# ct_psu.net
KiCad netlist of a schematic drawn in Altium Designer
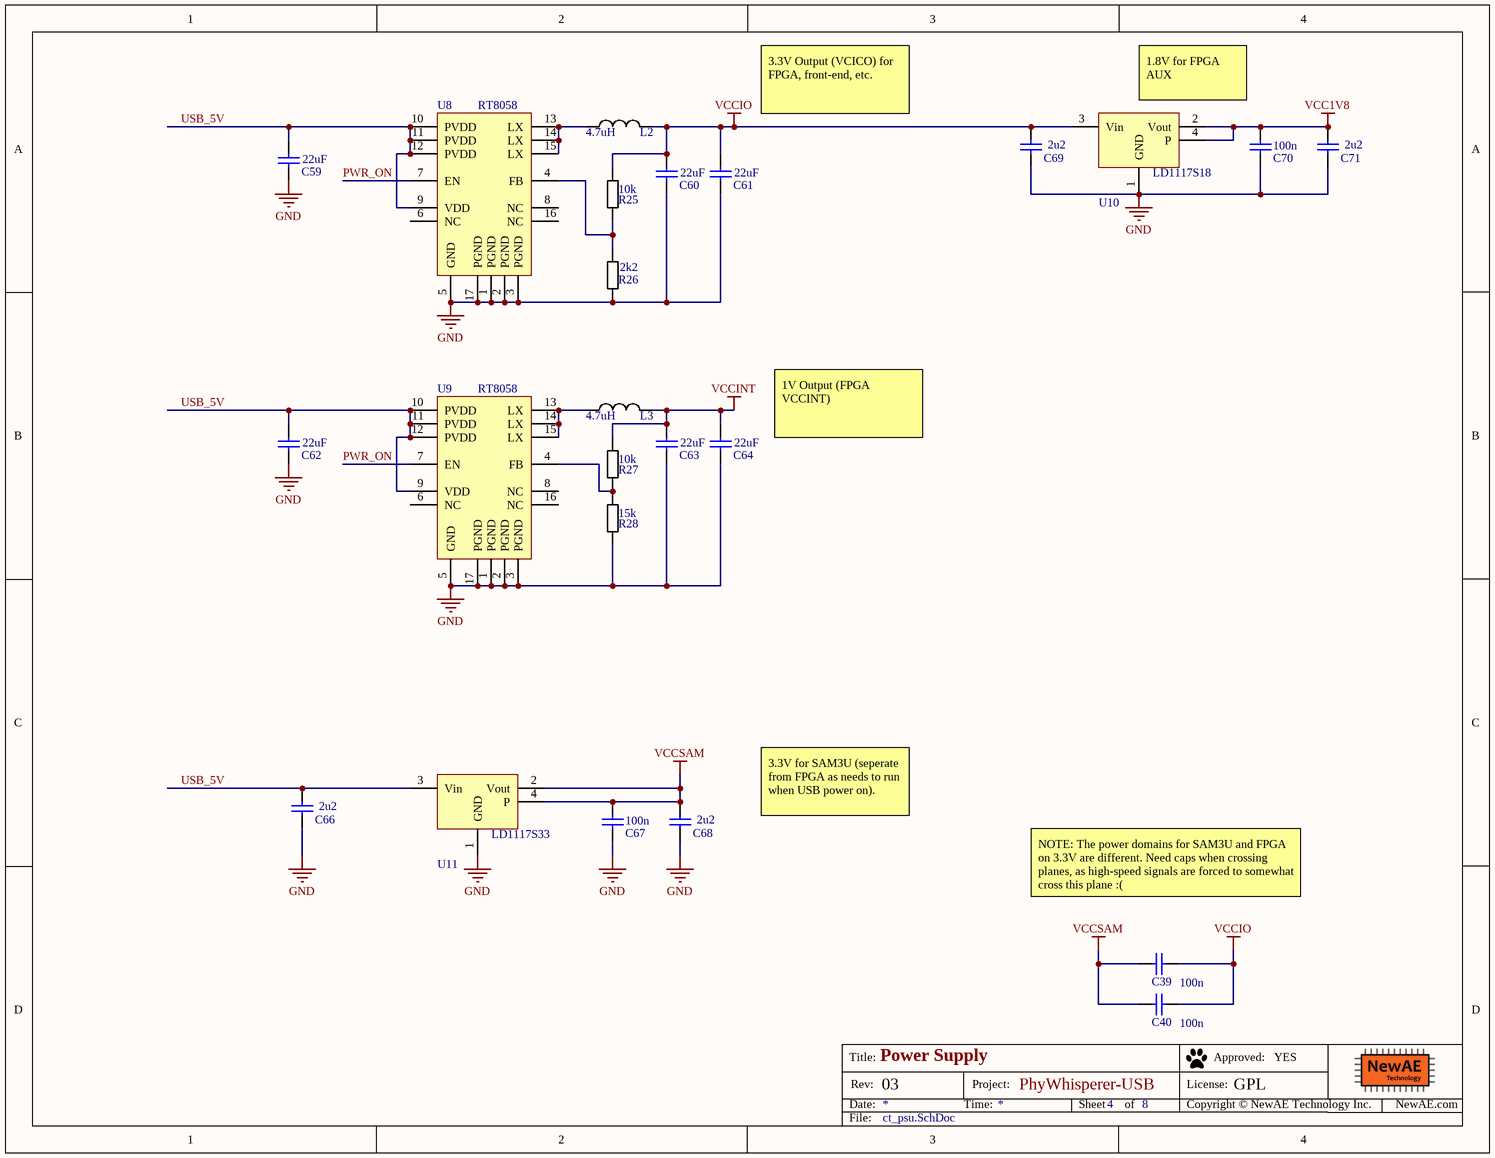
[diagram p0: ct_psu.SchDoc]

(export (version "E")
  (design (tool "Eeschema 10.0.6"))
  (components
    (comp (ref "C39")
      (value "100n")
      (footprint "CAPC0603_M")
      (description "100n, 0603")
      (fields (field (name "PART NUMBER") "CCHIP-100n-0603"))
      (libsource (lib "NewAE_AltiumLib") (part "CAP"))
    )
    (comp (ref "C40")
      (value "100n")
      (footprint "CAPC0603_M")
      (description "100n, 0603")
      (fields (field (name "PART NUMBER") "CCHIP-100n-0603"))
      (libsource (lib "NewAE_AltiumLib") (part "CAP"))
    )
    (comp (ref "C59")
      (value "22uF")
      (footprint "CAPC0805_M")
      (description "22u, 16V, 0805, Ceramic")
      (fields (field (name "PART NUMBER") "CCHIP-22u-0805-16V") (field (name "TOLERANCE") "20%"))
      (libsource (lib "NewAE_AltiumLib") (part "CAP"))
    )
    (comp (ref "C60")
      (value "22uF")
      (footprint "CAPC0805_M")
      (description "22u, 16V, 0805, Ceramic")
      (fields (field (name "PART NUMBER") "CCHIP-22u-0805-16V") (field (name "TOLERANCE") "20%"))
      (libsource (lib "NewAE_AltiumLib") (part "CAP"))
    )
    (comp (ref "C61")
      (value "22uF")
      (footprint "CAPC0805_M")
      (description "22u, 16V, 0805, Ceramic")
      (fields (field (name "PART NUMBER") "CCHIP-22u-0805-16V") (field (name "TOLERANCE") "20%"))
      (libsource (lib "NewAE_AltiumLib") (part "CAP"))
    )
    (comp (ref "C62")
      (value "22uF")
      (footprint "CAPC0805_M")
      (description "22u, 16V, 0805, Ceramic")
      (fields (field (name "PART NUMBER") "CCHIP-22u-0805-16V") (field (name "TOLERANCE") "20%"))
      (libsource (lib "NewAE_AltiumLib") (part "CAP"))
    )
    (comp (ref "C63")
      (value "22uF")
      (footprint "CAPC0805_M")
      (description "22u, 16V, 0805, Ceramic")
      (fields (field (name "PART NUMBER") "CCHIP-22u-0805-16V") (field (name "TOLERANCE") "20%"))
      (libsource (lib "NewAE_AltiumLib") (part "CAP"))
    )
    (comp (ref "C64")
      (value "22uF")
      (footprint "CAPC0805_M")
      (description "22u, 16V, 0805, Ceramic")
      (fields (field (name "PART NUMBER") "CCHIP-22u-0805-16V") (field (name "TOLERANCE") "20%"))
      (libsource (lib "NewAE_AltiumLib") (part "CAP"))
    )
    (comp (ref "C66")
      (value "2u2")
      (footprint "CAPC0603_M")
      (description "2u2, 0603")
      (fields (field (name "PART NUMBER") "CCHIP-2u2-0603"))
      (libsource (lib "NewAE_AltiumLib") (part "CAP"))
    )
    (comp (ref "C67")
      (value "100n")
      (footprint "CAPC0402_M")
      (description "100n, 0402")
      (fields (field (name "PART NUMBER") "CCHIP-100n-0402"))
      (libsource (lib "NewAE_AltiumLib") (part "CAP"))
    )
    (comp (ref "C68")
      (value "2u2")
      (footprint "CAPC0603_M")
      (description "2u2, 0603")
      (fields (field (name "PART NUMBER") "CCHIP-2u2-0603"))
      (libsource (lib "NewAE_AltiumLib") (part "CAP"))
    )
    (comp (ref "C69")
      (value "2u2")
      (footprint "CAPC0603_M")
      (description "2u2, 0603")
      (fields (field (name "PART NUMBER") "CCHIP-2u2-0603"))
      (libsource (lib "NewAE_AltiumLib") (part "CAP"))
    )
    (comp (ref "C70")
      (value "100n")
      (footprint "CAPC0402_M")
      (description "100n, 0402")
      (fields (field (name "PART NUMBER") "CCHIP-100n-0402"))
      (libsource (lib "NewAE_AltiumLib") (part "CAP"))
    )
    (comp (ref "C71")
      (value "2u2")
      (footprint "CAPC0603_M")
      (description "2u2, 0603")
      (fields (field (name "PART NUMBER") "CCHIP-2u2-0603"))
      (libsource (lib "NewAE_AltiumLib") (part "CAP"))
    )
    (comp (ref "L2")
      (value "4.7uH")
      (footprint "NR6028")
      (description "fixed ind, ferrite, shielded")
      (fields (field (name "PART NUMBER") "NR6028T4R7M"))
      (libsource (lib "NewAE_AltiumLib") (part "IND"))
    )
    (comp (ref "L3")
      (value "4.7uH")
      (footprint "NR6028")
      (description "fixed ind, ferrite, shielded")
      (fields (field (name "PART NUMBER") "NR6028T4R7M"))
      (libsource (lib "NewAE_AltiumLib") (part "IND"))
    )
    (comp (ref "R25")
      (value "10k")
      (footprint "RESC1608X55N")
      (description "10k res, 0603, 1%, 1/10W")
      (fields (field (name "PART NUMBER") "RCHIP-10K-0603") (field (name "TOLERANCE") "1%"))
      (libsource (lib "NewAE_AltiumLib") (part "RES-EU"))
    )
    (comp (ref "R26")
      (value "2k2")
      (footprint "RESC1608X55N")
      (description "2k2 res, 0603, 1%, 1/10W")
      (fields (field (name "PART NUMBER") "RCHIP-2K2-0603") (field (name "TOLERANCE") "1%"))
      (libsource (lib "NewAE_AltiumLib") (part "RES-EU"))
    )
    (comp (ref "R27")
      (value "10k")
      (footprint "RESC1608X55N")
      (description "10k res, 0603, 1%, 1/10W")
      (fields (field (name "PART NUMBER") "RCHIP-10K-0603") (field (name "TOLERANCE") "1%"))
      (libsource (lib "NewAE_AltiumLib") (part "RES-EU"))
    )
    (comp (ref "R28")
      (value "15k")
      (footprint "RESC1608X55N")
      (description "15k res, 0603, 1%, 1/10W")
      (fields (field (name "PART NUMBER") "RCHIP-15K-0603") (field (name "TOLERANCE") "1%"))
      (libsource (lib "NewAE_AltiumLib") (part "RES-EU"))
    )
    (comp (ref "U8")
      (value "RT8058")
      (footprint "QFN16_50P300X300X100_HS-17M")
      (description "Switching supply controller, 2A")
      (libsource (lib "NewAE_AltiumLib") (part "RT8058"))
    )
    (comp (ref "U9")
      (value "RT8058")
      (footprint "QFN16_50P300X300X100_HS-17M")
      (description "Switching supply controller, 2A")
      (libsource (lib "NewAE_AltiumLib") (part "RT8058"))
    )
    (comp (ref "U10")
      (value "LD1117S18")
      (footprint "SOT-223")
      (description "IC REG LIN POS 1.8V 800MA SOT223")
      (libsource (lib "NewAE_AltiumLib") (part "LD1117S33"))
    )
    (comp (ref "U11")
      (value "LD1117S33")
      (footprint "SOT-223")
      (description "IC REG LIN POS 3.3V 800MA SOT223")
      (libsource (lib "NewAE_AltiumLib") (part "LD1117S33"))
    )
  )
  (nets
    (net (code "1") (name "/PWR_ON") (class "Default")
      (node (ref "U8") (pin "7") (pinfunction "EN_7") (pintype "passive"))
      (node (ref "U9") (pin "7") (pinfunction "EN_7") (pintype "passive"))
    )
    (net (code "2") (name "/USB_5V") (class "Default")
      (node (ref "C59") (pin "1") (pinfunction "1_1") (pintype "passive"))
      (node (ref "C62") (pin "1") (pinfunction "1_1") (pintype "passive"))
      (node (ref "C66") (pin "1") (pinfunction "1_1") (pintype "passive"))
      (node (ref "U11") (pin "3") (pinfunction "Vin_3") (pintype "passive"))
      (node (ref "U8") (pin "10") (pinfunction "PVDD_10") (pintype "passive"))
      (node (ref "U8") (pin "11") (pinfunction "PVDD_11") (pintype "passive"))
      (node (ref "U8") (pin "12") (pinfunction "PVDD_12") (pintype "passive"))
      (node (ref "U8") (pin "9") (pinfunction "VDD_9") (pintype "passive"))
      (node (ref "U9") (pin "10") (pinfunction "PVDD_10") (pintype "passive"))
      (node (ref "U9") (pin "11") (pinfunction "PVDD_11") (pintype "passive"))
      (node (ref "U9") (pin "12") (pinfunction "PVDD_12") (pintype "passive"))
      (node (ref "U9") (pin "9") (pinfunction "VDD_9") (pintype "passive"))
    )
    (net (code "3") (name "GND") (class "Default")
      (node (ref "C59") (pin "2") (pinfunction "2_2") (pintype "passive"))
      (node (ref "C60") (pin "2") (pinfunction "2_2") (pintype "passive"))
      (node (ref "C61") (pin "2") (pinfunction "2_2") (pintype "passive"))
      (node (ref "C62") (pin "2") (pinfunction "2_2") (pintype "passive"))
      (node (ref "C63") (pin "2") (pinfunction "2_2") (pintype "passive"))
      (node (ref "C64") (pin "2") (pinfunction "2_2") (pintype "passive"))
      (node (ref "C66") (pin "2") (pinfunction "2_2") (pintype "passive"))
      (node (ref "C67") (pin "2") (pinfunction "2_2") (pintype "passive"))
      (node (ref "C68") (pin "2") (pinfunction "2_2") (pintype "passive"))
      (node (ref "C69") (pin "2") (pinfunction "2_2") (pintype "passive"))
      (node (ref "C70") (pin "2") (pinfunction "2_2") (pintype "passive"))
      (node (ref "C71") (pin "2") (pinfunction "2_2") (pintype "passive"))
      (node (ref "R26") (pin "2") (pinfunction "2_2") (pintype "passive"))
      (node (ref "R28") (pin "2") (pinfunction "2_2") (pintype "passive"))
      (node (ref "U10") (pin "1") (pinfunction "GND_1") (pintype "passive"))
      (node (ref "U11") (pin "1") (pinfunction "GND_1") (pintype "passive"))
      (node (ref "U8") (pin "1") (pinfunction "PGND_1") (pintype "passive"))
      (node (ref "U8") (pin "17") (pinfunction "PGND_17") (pintype "passive"))
      (node (ref "U8") (pin "2") (pinfunction "PGND_2") (pintype "passive"))
      (node (ref "U8") (pin "3") (pinfunction "PGND_3") (pintype "passive"))
      (node (ref "U8") (pin "5") (pinfunction "GND_5") (pintype "passive"))
      (node (ref "U9") (pin "1") (pinfunction "PGND_1") (pintype "passive"))
      (node (ref "U9") (pin "17") (pinfunction "PGND_17") (pintype "passive"))
      (node (ref "U9") (pin "2") (pinfunction "PGND_2") (pintype "passive"))
      (node (ref "U9") (pin "3") (pinfunction "PGND_3") (pintype "passive"))
      (node (ref "U9") (pin "5") (pinfunction "GND_5") (pintype "passive"))
    )
    (net (code "4") (name "Net-(L2-Pad1)") (class "Default")
      (node (ref "L2") (pin "1") (pinfunction "1_1") (pintype "passive"))
      (node (ref "U8") (pin "13") (pinfunction "LX_13") (pintype "passive"))
      (node (ref "U8") (pin "14") (pinfunction "LX_14") (pintype "passive"))
      (node (ref "U8") (pin "15") (pinfunction "LX_15") (pintype "passive"))
    )
    (net (code "5") (name "Net-(L3-Pad1)") (class "Default")
      (node (ref "L3") (pin "1") (pinfunction "1_1") (pintype "passive"))
      (node (ref "U9") (pin "13") (pinfunction "LX_13") (pintype "passive"))
      (node (ref "U9") (pin "14") (pinfunction "LX_14") (pintype "passive"))
      (node (ref "U9") (pin "15") (pinfunction "LX_15") (pintype "passive"))
    )
    (net (code "6") (name "Net-(U8-FB)") (class "Default")
      (node (ref "R25") (pin "2") (pinfunction "2_2") (pintype "passive"))
      (node (ref "R26") (pin "1") (pinfunction "1_1") (pintype "passive"))
      (node (ref "U8") (pin "4") (pinfunction "FB_4") (pintype "passive"))
    )
    (net (code "7") (name "Net-(U9-FB)") (class "Default")
      (node (ref "R27") (pin "2") (pinfunction "2_2") (pintype "passive"))
      (node (ref "R28") (pin "1") (pinfunction "1_1") (pintype "passive"))
      (node (ref "U9") (pin "4") (pinfunction "FB_4") (pintype "passive"))
    )
    (net (code "8") (name "VCC1V8") (class "Default")
      (node (ref "C70") (pin "1") (pinfunction "1_1") (pintype "passive"))
      (node (ref "C71") (pin "1") (pinfunction "1_1") (pintype "passive"))
      (node (ref "U10") (pin "2") (pinfunction "Vout_2") (pintype "passive"))
      (node (ref "U10") (pin "4") (pinfunction "P_4") (pintype "passive"))
    )
    (net (code "9") (name "VCCINT") (class "Default")
      (node (ref "C63") (pin "1") (pinfunction "1_1") (pintype "passive"))
      (node (ref "C64") (pin "1") (pinfunction "1_1") (pintype "passive"))
      (node (ref "L3") (pin "2") (pinfunction "2_2") (pintype "passive"))
      (node (ref "R27") (pin "1") (pinfunction "1_1") (pintype "passive"))
    )
    (net (code "10") (name "VCCIO") (class "Default")
      (node (ref "C39") (pin "2") (pinfunction "2_2") (pintype "passive"))
      (node (ref "C40") (pin "2") (pinfunction "2_2") (pintype "passive"))
      (node (ref "C60") (pin "1") (pinfunction "1_1") (pintype "passive"))
      (node (ref "C61") (pin "1") (pinfunction "1_1") (pintype "passive"))
      (node (ref "C69") (pin "1") (pinfunction "1_1") (pintype "passive"))
      (node (ref "L2") (pin "2") (pinfunction "2_2") (pintype "passive"))
      (node (ref "R25") (pin "1") (pinfunction "1_1") (pintype "passive"))
      (node (ref "U10") (pin "3") (pinfunction "Vin_3") (pintype "passive"))
    )
    (net (code "11") (name "VCCSAM") (class "Default")
      (node (ref "C39") (pin "1") (pinfunction "1_1") (pintype "passive"))
      (node (ref "C40") (pin "1") (pinfunction "1_1") (pintype "passive"))
      (node (ref "C67") (pin "1") (pinfunction "1_1") (pintype "passive"))
      (node (ref "C68") (pin "1") (pinfunction "1_1") (pintype "passive"))
      (node (ref "U11") (pin "2") (pinfunction "Vout_2") (pintype "passive"))
      (node (ref "U11") (pin "4") (pinfunction "P_4") (pintype "passive"))
    )
    (net (code "12") (name "unconnected-(U8-NC-Pad6)") (class "Default")
      (node (ref "U8") (pin "6") (pinfunction "NC_6") (pintype "passive"))
    )
    (net (code "13") (name "unconnected-(U8-NC-Pad8)") (class "Default")
      (node (ref "U8") (pin "8") (pinfunction "NC_8") (pintype "passive"))
    )
    (net (code "14") (name "unconnected-(U8-NC-Pad16)") (class "Default")
      (node (ref "U8") (pin "16") (pinfunction "NC_16") (pintype "passive"))
    )
    (net (code "15") (name "unconnected-(U9-NC-Pad6)") (class "Default")
      (node (ref "U9") (pin "6") (pinfunction "NC_6") (pintype "passive"))
    )
    (net (code "16") (name "unconnected-(U9-NC-Pad8)") (class "Default")
      (node (ref "U9") (pin "8") (pinfunction "NC_8") (pintype "passive"))
    )
    (net (code "17") (name "unconnected-(U9-NC-Pad16)") (class "Default")
      (node (ref "U9") (pin "16") (pinfunction "NC_16") (pintype "passive"))
    )
  )
)
